# ATTinyBreakout.net
KiCad netlist of a schematic drawn in EAGLE
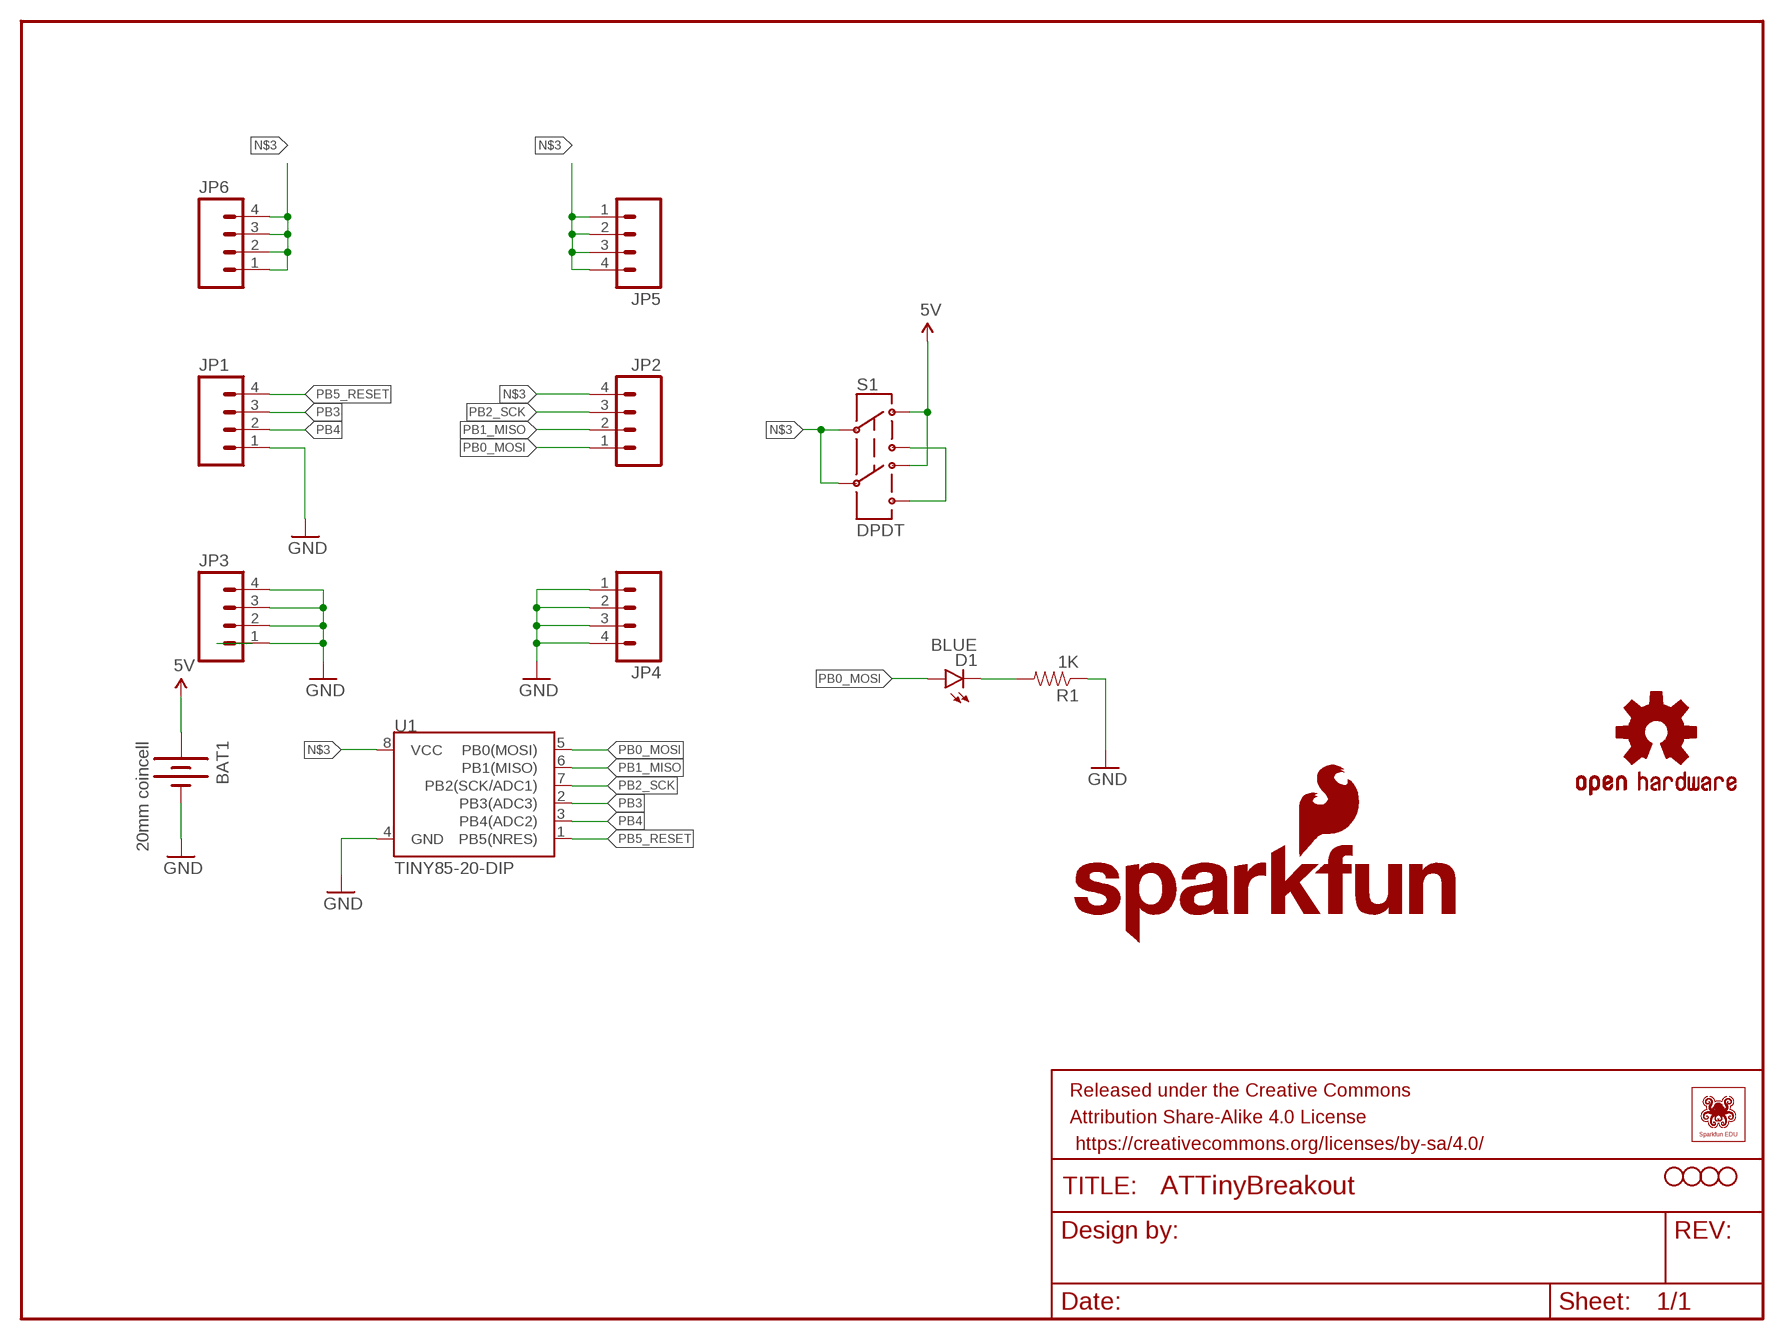
[diagram p0: schematic, sheet 1]

(export (version "E")
  (design (tool "Eeschema 10.0.6"))
  (components
    (comp (ref "BAT1")
      (value "20mm coincell")
      (footprint "eagle-import:BATTCON_20MM_4LEGS")
      (libsource (lib "eagle-import") (part "BATTERY20MM_4LEGS"))
    )
    (comp (ref "D1")
      (value "BLUE")
      (footprint "eagle-import:LED-1206")
      (libsource (lib "eagle-import") (part "LED-BLUE1206"))
    )
    (comp (ref "FRAME1")
      (value "FRAME-LETTER")
      (footprint "eagle-import:CREATIVE_COMMONS")
      (fields (field (name "DESIGNER") "NAME"))
      (libsource (lib "eagle-import") (part "FRAME-LETTER"))
    )
    (comp (ref "JP1")
      (value "M04LOCK")
      (footprint "eagle-import:1X04_LOCK")
      (libsource (lib "eagle-import") (part "M04LOCK"))
    )
    (comp (ref "JP2")
      (value "M04LOCK")
      (footprint "eagle-import:1X04_LOCK")
      (libsource (lib "eagle-import") (part "M04LOCK"))
    )
    (comp (ref "JP3")
      (value "M04LOCK")
      (footprint "eagle-import:1X04_LOCK")
      (libsource (lib "eagle-import") (part "M04LOCK"))
    )
    (comp (ref "JP4")
      (value "M04LOCK")
      (footprint "eagle-import:1X04_LOCK")
      (libsource (lib "eagle-import") (part "M04LOCK"))
    )
    (comp (ref "JP5")
      (value "M04LOCK")
      (footprint "eagle-import:1X04_LOCK")
      (libsource (lib "eagle-import") (part "M04LOCK"))
    )
    (comp (ref "JP6")
      (value "M04LOCK")
      (footprint "eagle-import:1X04_LOCK")
      (libsource (lib "eagle-import") (part "M04LOCK"))
    )
    (comp (ref "LOGO2")
      (value "SFE_LOGO_FLAME.1_INCH")
      (footprint "eagle-import:SFE_LOGO_FLAME_.1")
      (libsource (lib "eagle-import") (part "SFE_LOGO_FLAME.1_INCH"))
    )
    (comp (ref "LOGO3")
      (value "OSHW-LOGOS")
      (footprint "eagle-import:OSHW-LOGO-S")
      (libsource (lib "eagle-import") (part "OSHW-LOGOS"))
    )
    (comp (ref "LOGO4")
      (value "SFE_LOGO_NAME_FLAME.1_INCH")
      (footprint "eagle-import:SFE_LOGO_NAME_FLAME_.1")
      (libsource (lib "eagle-import") (part "SFE_LOGO_NAME_FLAME.1_INCH"))
    )
    (comp (ref "R1")
      (value "1K")
      (footprint "eagle-import:0603-RES")
      (libsource (lib "eagle-import") (part "1KOHM-1/10W-1%(0603)"))
    )
    (comp (ref "S1")
      (value "DPDT")
      (footprint "eagle-import:AYZ0202")
      (libsource (lib "eagle-import") (part "SWITCH-DPDTAYZ0202"))
    )
    (comp (ref "STANDOFF1")
      (value "STAND-OFF")
      (footprint "eagle-import:STAND-OFF")
      (libsource (lib "eagle-import") (part "STAND-OFF"))
    )
    (comp (ref "STANDOFF2")
      (value "STAND-OFF")
      (footprint "eagle-import:STAND-OFF")
      (libsource (lib "eagle-import") (part "STAND-OFF"))
    )
    (comp (ref "STANDOFF3")
      (value "STAND-OFF")
      (footprint "eagle-import:STAND-OFF")
      (libsource (lib "eagle-import") (part "STAND-OFF"))
    )
    (comp (ref "STANDOFF4")
      (value "STAND-OFF")
      (footprint "eagle-import:STAND-OFF")
      (libsource (lib "eagle-import") (part "STAND-OFF"))
    )
    (comp (ref "U$2")
      (value "SFE_LUDUSSFE_LUDUS-M")
      (footprint "eagle-import:SFE_LUDUS-M")
      (libsource (lib "eagle-import") (part "SFE_LUDUSSFE_LUDUS-M"))
    )
    (comp (ref "U1")
      (value "TINY85-20-DIP")
      (footprint "eagle-import:DIP08")
      (libsource (lib "eagle-import") (part "ATTINY45TINY85-20-DIP"))
    )
  )
  (nets
    (net (code "1") (name "5V") (class "Default")
      (node (ref "BAT1") (pin "1") (pinfunction "+_1") (pintype "power_in"))
      (node (ref "S1") (pin "1") (pinfunction "1_1") (pintype "bidirectional"))
      (node (ref "S1") (pin "4") (pinfunction "4_4") (pintype "bidirectional"))
    )
    (net (code "2") (name "GND") (class "Default")
      (node (ref "BAT1") (pin "2") (pinfunction "-_2") (pintype "power_in"))
      (node (ref "JP1") (pin "1") (pinfunction "1_1") (pintype "passive"))
      (node (ref "JP3") (pin "1") (pinfunction "1_1") (pintype "passive"))
      (node (ref "JP3") (pin "2") (pinfunction "2_2") (pintype "passive"))
      (node (ref "JP3") (pin "3") (pinfunction "3_3") (pintype "passive"))
      (node (ref "JP3") (pin "4") (pinfunction "4_4") (pintype "passive"))
      (node (ref "JP4") (pin "1") (pinfunction "1_1") (pintype "passive"))
      (node (ref "JP4") (pin "2") (pinfunction "2_2") (pintype "passive"))
      (node (ref "JP4") (pin "3") (pinfunction "3_3") (pintype "passive"))
      (node (ref "JP4") (pin "4") (pinfunction "4_4") (pintype "passive"))
      (node (ref "R1") (pin "1") (pinfunction "1_1") (pintype "passive"))
      (node (ref "U1") (pin "4") (pinfunction "GND_4") (pintype "bidirectional"))
    )
    (net (code "3") (name "N$3") (class "Default")
      (node (ref "JP2") (pin "4") (pinfunction "4_4") (pintype "passive"))
      (node (ref "JP5") (pin "1") (pinfunction "1_1") (pintype "passive"))
      (node (ref "JP5") (pin "2") (pinfunction "2_2") (pintype "passive"))
      (node (ref "JP5") (pin "3") (pinfunction "3_3") (pintype "passive"))
      (node (ref "JP5") (pin "4") (pinfunction "4_4") (pintype "passive"))
      (node (ref "JP6") (pin "1") (pinfunction "1_1") (pintype "passive"))
      (node (ref "JP6") (pin "2") (pinfunction "2_2") (pintype "passive"))
      (node (ref "JP6") (pin "3") (pinfunction "3_3") (pintype "passive"))
      (node (ref "JP6") (pin "4") (pinfunction "4_4") (pintype "passive"))
      (node (ref "S1") (pin "2") (pinfunction "2_2") (pintype "bidirectional"))
      (node (ref "S1") (pin "5") (pinfunction "5_5") (pintype "bidirectional"))
      (node (ref "U1") (pin "8") (pinfunction "VCC_8") (pintype "bidirectional"))
    )
    (net (code "4") (name "Net-(D1-PadC)") (class "Default")
      (node (ref "D1") (pin "C") (pinfunction "C_C") (pintype "passive"))
      (node (ref "R1") (pin "2") (pinfunction "2_2") (pintype "passive"))
    )
    (net (code "5") (name "Net-(S1-Pad3)") (class "Default")
      (node (ref "S1") (pin "3") (pinfunction "3_3") (pintype "bidirectional"))
      (node (ref "S1") (pin "6") (pinfunction "6_6") (pintype "bidirectional"))
    )
    (net (code "6") (name "PB0_MOSI") (class "Default")
      (node (ref "D1") (pin "A") (pinfunction "A_A") (pintype "passive"))
      (node (ref "JP2") (pin "1") (pinfunction "1_1") (pintype "passive"))
      (node (ref "U1") (pin "5") (pinfunction "PB0(MOSI)_5") (pintype "bidirectional"))
    )
    (net (code "7") (name "PB1_MISO") (class "Default")
      (node (ref "JP2") (pin "2") (pinfunction "2_2") (pintype "passive"))
      (node (ref "U1") (pin "6") (pinfunction "PB1(MISO)_6") (pintype "bidirectional"))
    )
    (net (code "8") (name "PB2_SCK") (class "Default")
      (node (ref "JP2") (pin "3") (pinfunction "3_3") (pintype "passive"))
      (node (ref "U1") (pin "7") (pinfunction "PB2(SCK/ADC1)_7") (pintype "bidirectional"))
    )
    (net (code "9") (name "PB3") (class "Default")
      (node (ref "JP1") (pin "3") (pinfunction "3_3") (pintype "passive"))
      (node (ref "U1") (pin "2") (pinfunction "PB3(ADC3)_2") (pintype "bidirectional"))
    )
    (net (code "10") (name "PB4") (class "Default")
      (node (ref "JP1") (pin "2") (pinfunction "2_2") (pintype "passive"))
      (node (ref "U1") (pin "3") (pinfunction "PB4(ADC2)_3") (pintype "bidirectional"))
    )
    (net (code "11") (name "PB5_RESET") (class "Default")
      (node (ref "JP1") (pin "4") (pinfunction "4_4") (pintype "passive"))
      (node (ref "U1") (pin "1") (pinfunction "PB5(NRES)_1") (pintype "bidirectional"))
    )
  )
)
